# AMU-S31-V00-Peripherals.net
KiCad netlist of a schematic drawn in Altium Designer
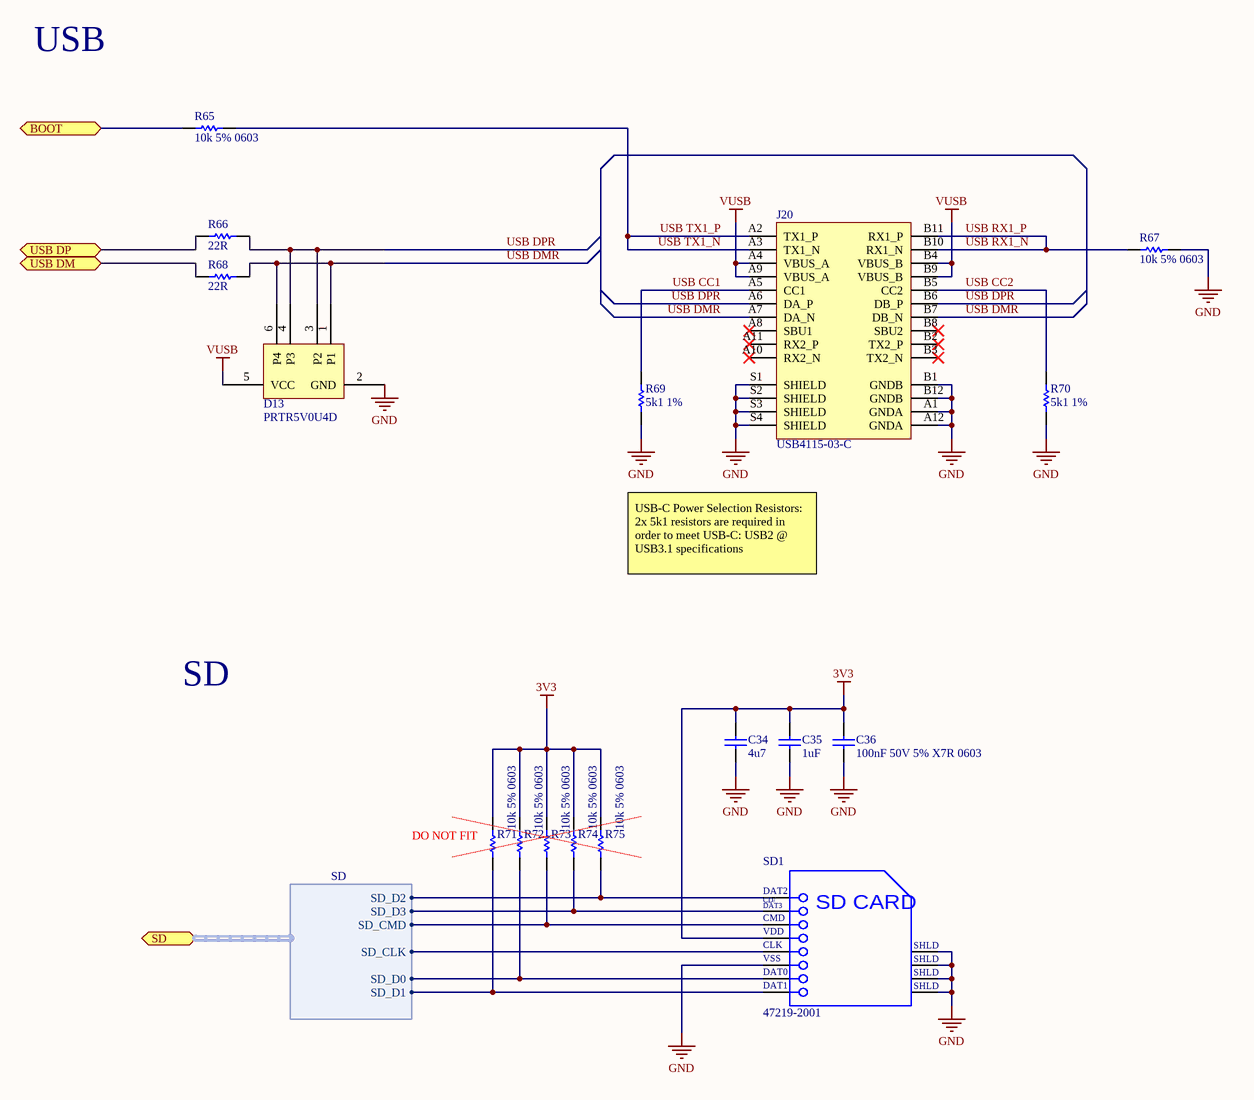
[diagram p0: AMU-S31-V00-Peripherals.SchDoc]

(export (version "E")
  (design (tool "Eeschema 10.0.6"))
  (components
    (comp (ref "C34")
      (value "4u7")
      (footprint "Cap_Ceramic_0603")
      (description "Capacitor, Ceramic, SMD, 4u7, 50V, 5%, X7R, 0603")
      (libsource (lib "StandardCapacitors") (part "4u7 50V 5% X7R 0603"))
    )
    (comp (ref "C35")
      (value "1uF")
      (footprint "Cap_Ceramic_0603")
      (description "Capacitor, Ceramic, SMD, 1uF, 25V, 5%, X7R, 0603")
      (libsource (lib "StandardCapacitors") (part "1uF 25V 5% X7R 0603"))
    )
    (comp (ref "C36")
      (value "100nF 50V 5% X7R 0603")
      (footprint "Cap_Ceramic_0603")
      (description "Capacitor, Ceramic, SMD, 100nF, 50V, 5%, X7R, 0603")
      (libsource (lib "StandardCapacitors") (part "100nF 50V 5% X7R 0603"))
    )
    (comp (ref "D13")
      (value "PRTR5V0U4D")
      (footprint "SC-47")
      (description "Clamp Ipp Tvs Diode Surface Mount 6-TSOP")
      (libsource (lib "QUTMS-Project-VCULibrary") (part "PRTR5V0U4D"))
    )
    (comp (ref "J20")
      (value "USB4115-03-C")
      (footprint "USB4115-03-C")
      (libsource (lib "QUTMS_USBLibrary") (part "USB4115-03-C"))
    )
    (comp (ref "R65")
      (value "10k 5% 0603")
      (footprint "Res_ThinFilm_0603")
      (description "Resistor, SMD, 10k, 0.1W, 5%, 0603")
      (libsource (lib "StandardResistors") (part "10k 5% 0603"))
    )
    (comp (ref "R66")
      (value "22R")
      (footprint "Res_ThinFilm_0603")
      (description "Resistor, SMD, 22R, 0.1W, 5%, 0603")
      (libsource (lib "StandardResistors") (part "22R 5% 0603"))
    )
    (comp (ref "R67")
      (value "10k 5% 0603")
      (footprint "Res_ThinFilm_0603")
      (description "Resistor, SMD, 10k, 0.1W, 5%, 0603")
      (libsource (lib "StandardResistors") (part "10k 5% 0603"))
    )
    (comp (ref "R68")
      (value "22R")
      (footprint "Res_ThinFilm_0603")
      (description "Resistor, SMD, 22R, 0.1W, 5%, 0603")
      (libsource (lib "StandardResistors") (part "22R 5% 0603"))
    )
    (comp (ref "R69")
      (value "5k1 1%")
      (footprint "Res_ThinFilm_0603")
      (description "Resistor, SMD, 5k1, 0.1W, 1%, 0603")
      (libsource (lib "StandardResistors") (part "5k1 1% 0603"))
    )
    (comp (ref "R70")
      (value "5k1 1%")
      (footprint "Res_ThinFilm_0603")
      (description "Resistor, SMD, 5k1, 0.1W, 1%, 0603")
      (libsource (lib "StandardResistors") (part "5k1 1% 0603"))
    )
    (comp (ref "R71")
      (value "10k 5% 0603")
      (footprint "Res_ThinFilm_0603")
      (description "Resistor, SMD, 10k, 0.1W, 5%, 0603")
      (libsource (lib "StandardResistors") (part "10k 5% 0603"))
    )
    (comp (ref "R72")
      (value "10k 5% 0603")
      (footprint "Res_ThinFilm_0603")
      (description "Resistor, SMD, 10k, 0.1W, 5%, 0603")
      (libsource (lib "StandardResistors") (part "10k 5% 0603"))
    )
    (comp (ref "R73")
      (value "10k 5% 0603")
      (footprint "Res_ThinFilm_0603")
      (description "Resistor, SMD, 10k, 0.1W, 5%, 0603")
      (libsource (lib "StandardResistors") (part "10k 5% 0603"))
    )
    (comp (ref "R74")
      (value "10k 5% 0603")
      (footprint "Res_ThinFilm_0603")
      (description "Resistor, SMD, 10k, 0.1W, 5%, 0603")
      (libsource (lib "StandardResistors") (part "10k 5% 0603"))
    )
    (comp (ref "R75")
      (value "10k 5% 0603")
      (footprint "Res_ThinFilm_0603")
      (description "Resistor, SMD, 10k, 0.1W, 5%, 0603")
      (libsource (lib "StandardResistors") (part "10k 5% 0603"))
    )
    (comp (ref "SD1")
      (value "47219-2001")
      (footprint "MOLX-47219-2001-8_V")
      (description "MicroSD Card Connector, Hinge Type, -40 to 85 degC, 8-Pin SMD, RoHS, Tape and Reel")
      (fields (field (name "MANUFACTURER") "Molex"))
      (libsource (lib "Altium Content Vault") (part "CN-SD-8-4S"))
    )
  )
  (nets
    (net (code "2") (name "/BOOT") (class "Default")
      (node (ref "R65") (pin "2") (pinfunction "2_2") (pintype "passive"))
    )
    (net (code "3") (name "/SD_CLK") (class "Default")
      (node (ref "SD1") (pin "5") (pinfunction "CLK_5") (pintype "passive"))
    )
    (net (code "4") (name "/SD_CMD") (class "Default")
      (node (ref "R73") (pin "1") (pinfunction "1_1") (pintype "passive"))
      (node (ref "SD1") (pin "3") (pinfunction "CMD_3") (pintype "passive"))
    )
    (net (code "5") (name "/SD_D0") (class "Default")
      (node (ref "R72") (pin "1") (pinfunction "1_1") (pintype "passive"))
      (node (ref "SD1") (pin "7") (pinfunction "DAT0_7") (pintype "passive"))
    )
    (net (code "6") (name "/SD_D1") (class "Default")
      (node (ref "R71") (pin "1") (pinfunction "1_1") (pintype "passive"))
      (node (ref "SD1") (pin "8") (pinfunction "DAT1_8") (pintype "passive"))
    )
    (net (code "7") (name "/SD_D2") (class "Default")
      (node (ref "R75") (pin "1") (pinfunction "1_1") (pintype "passive"))
      (node (ref "SD1") (pin "1") (pinfunction "DAT2_1") (pintype "passive"))
    )
    (net (code "8") (name "/SD_D3") (class "Default")
      (node (ref "R74") (pin "1") (pinfunction "1_1") (pintype "passive"))
      (node (ref "SD1") (pin "2") (pinfunction "CD/DAT3_2") (pintype "passive"))
    )
    (net (code "9") (name "/USB CC1") (class "Default")
      (node (ref "J20") (pin "A5") (pinfunction "CC1_A5") (pintype "passive"))
      (node (ref "R69") (pin "2") (pinfunction "2_2") (pintype "passive"))
    )
    (net (code "10") (name "/USB CC2") (class "Default")
      (node (ref "J20") (pin "B5") (pinfunction "CC2_B5") (pintype "passive"))
      (node (ref "R70") (pin "2") (pinfunction "2_2") (pintype "passive"))
    )
    (net (code "11") (name "/USB DM") (class "Default")
      (node (ref "R68") (pin "1") (pinfunction "1_1") (pintype "passive"))
    )
    (net (code "12") (name "/USB DMR") (class "Default")
      (node (ref "D13") (pin "1") (pinfunction "P1_1") (pintype "passive"))
      (node (ref "D13") (pin "6") (pinfunction "P4_6") (pintype "passive"))
      (node (ref "J20") (pin "A7") (pinfunction "DA_N_A7") (pintype "passive"))
      (node (ref "J20") (pin "B7") (pinfunction "DB_N_B7") (pintype "passive"))
      (node (ref "R68") (pin "2") (pinfunction "2_2") (pintype "passive"))
    )
    (net (code "13") (name "/USB DP") (class "Default")
      (node (ref "R66") (pin "1") (pinfunction "1_1") (pintype "passive"))
    )
    (net (code "14") (name "/USB DPR") (class "Default")
      (node (ref "D13") (pin "3") (pinfunction "P2_3") (pintype "passive"))
      (node (ref "D13") (pin "4") (pinfunction "P3_4") (pintype "passive"))
      (node (ref "J20") (pin "A6") (pinfunction "DA_P_A6") (pintype "passive"))
      (node (ref "J20") (pin "B6") (pinfunction "DB_P_B6") (pintype "passive"))
      (node (ref "R66") (pin "2") (pinfunction "2_2") (pintype "passive"))
    )
    (net (code "15") (name "/USB RX1_N") (class "Default")
      (node (ref "J20") (pin "B10") (pinfunction "RX1_N_B10") (pintype "passive"))
      (node (ref "J20") (pin "B11") (pinfunction "RX1_P_B11") (pintype "passive"))
      (node (ref "R67") (pin "1") (pinfunction "1_1") (pintype "passive"))
    )
    (net (code "16") (name "/USB TX1_N") (class "Default")
      (node (ref "J20") (pin "A2") (pinfunction "TX1_P_A2") (pintype "passive"))
      (node (ref "J20") (pin "A3") (pinfunction "TX1_N_A3") (pintype "passive"))
      (node (ref "R65") (pin "1") (pinfunction "1_1") (pintype "passive"))
    )
    (net (code "18") (name "3V3") (class "Default")
      (node (ref "C34") (pin "2") (pinfunction "2_2") (pintype "passive"))
      (node (ref "C35") (pin "2") (pinfunction "2_2") (pintype "passive"))
      (node (ref "C36") (pin "2") (pinfunction "2_2") (pintype "passive"))
      (node (ref "R71") (pin "2") (pinfunction "2_2") (pintype "passive"))
      (node (ref "R72") (pin "2") (pinfunction "2_2") (pintype "passive"))
      (node (ref "R73") (pin "2") (pinfunction "2_2") (pintype "passive"))
      (node (ref "R74") (pin "2") (pinfunction "2_2") (pintype "passive"))
      (node (ref "R75") (pin "2") (pinfunction "2_2") (pintype "passive"))
      (node (ref "SD1") (pin "4") (pinfunction "VDD_4") (pintype "passive"))
    )
    (net (code "19") (name "GND") (class "Default")
      (node (ref "C34") (pin "1") (pinfunction "1_1") (pintype "passive"))
      (node (ref "C35") (pin "1") (pinfunction "1_1") (pintype "passive"))
      (node (ref "C36") (pin "1") (pinfunction "1_1") (pintype "passive"))
      (node (ref "D13") (pin "2") (pinfunction "GND_2") (pintype "passive"))
      (node (ref "J20") (pin "A1") (pinfunction "GNDA_A1") (pintype "passive"))
      (node (ref "J20") (pin "A12") (pinfunction "GNDA_A12") (pintype "passive"))
      (node (ref "J20") (pin "B1") (pinfunction "GNDB_B1") (pintype "passive"))
      (node (ref "J20") (pin "B12") (pinfunction "GNDB_B12") (pintype "passive"))
      (node (ref "J20") (pin "S1") (pinfunction "SHIELD_S1") (pintype "power_in"))
      (node (ref "J20") (pin "S2") (pinfunction "SHIELD_S2") (pintype "power_in"))
      (node (ref "J20") (pin "S3") (pinfunction "SHIELD_S3") (pintype "power_in"))
      (node (ref "J20") (pin "S4") (pinfunction "SHIELD_S4") (pintype "power_in"))
      (node (ref "R67") (pin "2") (pinfunction "2_2") (pintype "passive"))
      (node (ref "R69") (pin "1") (pinfunction "1_1") (pintype "passive"))
      (node (ref "R70") (pin "1") (pinfunction "1_1") (pintype "passive"))
      (node (ref "SD1") (pin "10") (pinfunction "SHLD_10") (pintype "passive"))
      (node (ref "SD1") (pin "11") (pinfunction "SHLD_11") (pintype "passive"))
      (node (ref "SD1") (pin "12") (pinfunction "SHLD_12") (pintype "passive"))
      (node (ref "SD1") (pin "6") (pinfunction "VSS_6") (pintype "passive"))
      (node (ref "SD1") (pin "9") (pinfunction "SHLD_9") (pintype "passive"))
    )
    (net (code "20") (name "VUSB") (class "Default")
      (node (ref "D13") (pin "5") (pinfunction "VCC_5") (pintype "passive"))
      (node (ref "J20") (pin "A4") (pinfunction "VBUS_A_A4") (pintype "passive"))
      (node (ref "J20") (pin "A9") (pinfunction "VBUS_A_A9") (pintype "passive"))
      (node (ref "J20") (pin "B4") (pinfunction "VBUS_B_B4") (pintype "passive"))
      (node (ref "J20") (pin "B9") (pinfunction "VBUS_B_B9") (pintype "passive"))
    )
    (net (code "21") (name "unconnected-(J20-RX2_N-PadA10)") (class "Default")
      (node (ref "J20") (pin "A10") (pinfunction "RX2_N_A10") (pintype "passive+no_connect"))
    )
    (net (code "22") (name "unconnected-(J20-RX2_P-PadA11)") (class "Default")
      (node (ref "J20") (pin "A11") (pinfunction "RX2_P_A11") (pintype "passive+no_connect"))
    )
    (net (code "23") (name "unconnected-(J20-SBU1-PadA8)") (class "Default")
      (node (ref "J20") (pin "A8") (pinfunction "SBU1_A8") (pintype "passive+no_connect"))
    )
    (net (code "24") (name "unconnected-(J20-SBU2-PadB8)") (class "Default")
      (node (ref "J20") (pin "B8") (pinfunction "SBU2_B8") (pintype "passive+no_connect"))
    )
    (net (code "25") (name "unconnected-(J20-TX2_N-PadB3)") (class "Default")
      (node (ref "J20") (pin "B3") (pinfunction "TX2_N_B3") (pintype "passive+no_connect"))
    )
    (net (code "26") (name "unconnected-(J20-TX2_P-PadB2)") (class "Default")
      (node (ref "J20") (pin "B2") (pinfunction "TX2_P_B2") (pintype "passive+no_connect"))
    )
  )
)
